# controller_ardu.net
KiCad netlist of a schematic drawn in EAGLE
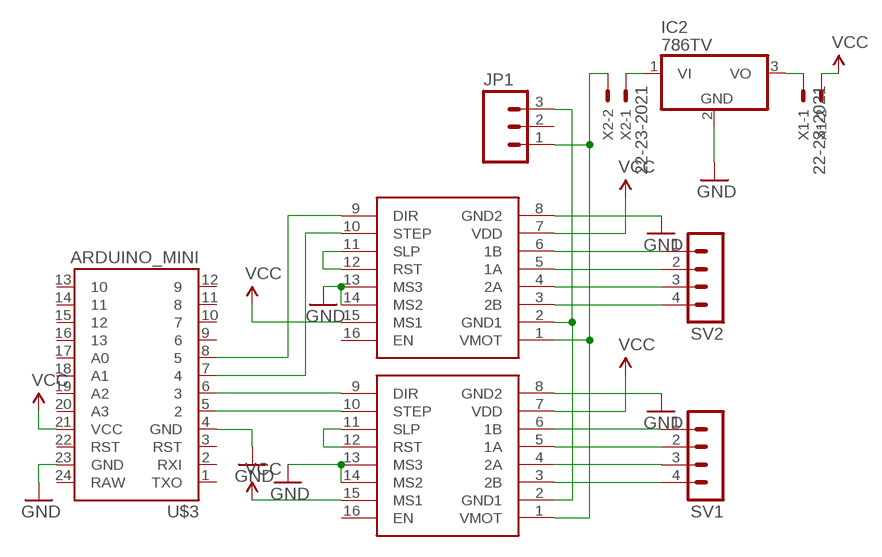
[diagram p0: schematic, sheet 1]

(export (version "E")
  (design (tool "Eeschema 10.0.6"))
  (components
    (comp (ref "IC2")
      (value "786TV")
      (footprint "eagle-import:TO220V")
      (libsource (lib "eagle-import") (part "78TV6"))
    )
    (comp (ref "JP1")
      (value "M03SCREW")
      (footprint "eagle-import:SCREWTERMINAL-3.5MM-3")
      (libsource (lib "eagle-import") (part "M03SCREW"))
    )
    (comp (ref "SV1")
      (value "MA04-1")
      (footprint "eagle-import:MA04-1")
      (libsource (lib "eagle-import") (part "MA04-1"))
    )
    (comp (ref "SV2")
      (value "MA04-1")
      (footprint "eagle-import:MA04-1")
      (libsource (lib "eagle-import") (part "MA04-1"))
    )
    (comp (ref "U$1")
      (value "POLOLUESTEPPERDRIVER")
      (footprint "eagle-import:DIL16")
      (libsource (lib "eagle-import") (part "POLOLUESTEPPERDRIVER"))
    )
    (comp (ref "U$2")
      (value "POLOLUESTEPPERDRIVER")
      (footprint "eagle-import:DIL16")
      (libsource (lib "eagle-import") (part "POLOLUESTEPPERDRIVER"))
    )
    (comp (ref "U$3")
      (value "ARDUINO_MINI")
      (footprint "eagle-import:ARDUINO_MINI")
      (libsource (lib "eagle-import") (part "ARDUINO_MINI"))
    )
    (comp (ref "X1")
      (value "22-23-2021")
      (footprint "eagle-import:22-23-2021")
      (fields (field (name "MF") "MOLEX"))
      (libsource (lib "eagle-import") (part "22-23-2021"))
    )
    (comp (ref "X2")
      (value "22-23-2021")
      (footprint "eagle-import:22-23-2021")
      (fields (field (name "MF") "MOLEX"))
      (libsource (lib "eagle-import") (part "22-23-2021"))
    )
  )
  (nets
    (net (code "1") (name "GND") (class "Default")
      (node (ref "IC2") (pin "2") (pinfunction "GND_2") (pintype "passive"))
      (node (ref "U$1") (pin "13") (pinfunction "MS3_13") (pintype "input"))
      (node (ref "U$1") (pin "14") (pinfunction "MS2_14") (pintype "input"))
      (node (ref "U$1") (pin "8") (pinfunction "GND2_8") (pintype "power_in"))
      (node (ref "U$2") (pin "13") (pinfunction "MS3_13") (pintype "input"))
      (node (ref "U$2") (pin "14") (pinfunction "MS2_14") (pintype "input"))
      (node (ref "U$2") (pin "8") (pinfunction "GND2_8") (pintype "power_in"))
      (node (ref "U$3") (pin "23") (pinfunction "GND_23") (pintype "bidirectional"))
      (node (ref "U$3") (pin "4") (pinfunction "GND_4") (pintype "bidirectional"))
    )
    (net (code "2") (name "Net-(IC2-VI)") (class "Default")
      (node (ref "IC2") (pin "1") (pinfunction "VI_1") (pintype "input"))
      (node (ref "X2") (pin "1") (pinfunction "S_1") (pintype "passive"))
    )
    (net (code "3") (name "Net-(IC2-VO)") (class "Default")
      (node (ref "IC2") (pin "3") (pinfunction "VO_3") (pintype "passive"))
      (node (ref "X1") (pin "1") (pinfunction "S_1") (pintype "passive"))
    )
    (net (code "4") (name "Net-(U$1-1A)") (class "Default")
      (node (ref "SV1") (pin "2") (pinfunction "2_2") (pintype "passive"))
      (node (ref "U$1") (pin "5") (pinfunction "1A_5") (pintype "output"))
    )
    (net (code "5") (name "Net-(U$1-1B)") (class "Default")
      (node (ref "SV1") (pin "1") (pinfunction "1_1") (pintype "passive"))
      (node (ref "U$1") (pin "6") (pinfunction "1B_6") (pintype "output"))
    )
    (net (code "6") (name "Net-(U$1-2A)") (class "Default")
      (node (ref "SV1") (pin "3") (pinfunction "3_3") (pintype "passive"))
      (node (ref "U$1") (pin "4") (pinfunction "2A_4") (pintype "output"))
    )
    (net (code "7") (name "Net-(U$1-2B)") (class "Default")
      (node (ref "SV1") (pin "4") (pinfunction "4_4") (pintype "passive"))
      (node (ref "U$1") (pin "3") (pinfunction "2B_3") (pintype "output"))
    )
    (net (code "8") (name "Net-(U$1-DIR)") (class "Default")
      (node (ref "U$1") (pin "9") (pinfunction "DIR_9") (pintype "input"))
      (node (ref "U$3") (pin "6") (pinfunction "3_6") (pintype "bidirectional"))
    )
    (net (code "9") (name "Net-(U$1-GND1)") (class "Default")
      (node (ref "JP1") (pin "3") (pinfunction "3_3") (pintype "passive"))
      (node (ref "U$1") (pin "2") (pinfunction "GND1_2") (pintype "power_in"))
      (node (ref "U$2") (pin "2") (pinfunction "GND1_2") (pintype "power_in"))
    )
    (net (code "10") (name "Net-(U$1-RST)") (class "Default")
      (node (ref "U$1") (pin "11") (pinfunction "SLP_11") (pintype "input"))
      (node (ref "U$1") (pin "12") (pinfunction "RST_12") (pintype "input"))
    )
    (net (code "11") (name "Net-(U$1-STEP)") (class "Default")
      (node (ref "U$1") (pin "10") (pinfunction "STEP_10") (pintype "input"))
      (node (ref "U$3") (pin "5") (pinfunction "2_5") (pintype "bidirectional"))
    )
    (net (code "12") (name "Net-(U$1-VMOT)") (class "Default")
      (node (ref "JP1") (pin "1") (pinfunction "1_1") (pintype "passive"))
      (node (ref "U$1") (pin "1") (pinfunction "VMOT_1") (pintype "power_in"))
      (node (ref "U$2") (pin "1") (pinfunction "VMOT_1") (pintype "power_in"))
      (node (ref "X2") (pin "2") (pinfunction "S_2") (pintype "passive"))
    )
    (net (code "13") (name "Net-(U$2-1A)") (class "Default")
      (node (ref "SV2") (pin "2") (pinfunction "2_2") (pintype "passive"))
      (node (ref "U$2") (pin "5") (pinfunction "1A_5") (pintype "output"))
    )
    (net (code "14") (name "Net-(U$2-1B)") (class "Default")
      (node (ref "SV2") (pin "1") (pinfunction "1_1") (pintype "passive"))
      (node (ref "U$2") (pin "6") (pinfunction "1B_6") (pintype "output"))
    )
    (net (code "15") (name "Net-(U$2-2A)") (class "Default")
      (node (ref "SV2") (pin "3") (pinfunction "3_3") (pintype "passive"))
      (node (ref "U$2") (pin "4") (pinfunction "2A_4") (pintype "output"))
    )
    (net (code "16") (name "Net-(U$2-2B)") (class "Default")
      (node (ref "SV2") (pin "4") (pinfunction "4_4") (pintype "passive"))
      (node (ref "U$2") (pin "3") (pinfunction "2B_3") (pintype "output"))
    )
    (net (code "17") (name "Net-(U$2-DIR)") (class "Default")
      (node (ref "U$2") (pin "9") (pinfunction "DIR_9") (pintype "input"))
      (node (ref "U$3") (pin "8") (pinfunction "5_8") (pintype "bidirectional"))
    )
    (net (code "18") (name "Net-(U$2-RST)") (class "Default")
      (node (ref "U$2") (pin "11") (pinfunction "SLP_11") (pintype "input"))
      (node (ref "U$2") (pin "12") (pinfunction "RST_12") (pintype "input"))
    )
    (net (code "19") (name "Net-(U$2-STEP)") (class "Default")
      (node (ref "U$2") (pin "10") (pinfunction "STEP_10") (pintype "input"))
      (node (ref "U$3") (pin "7") (pinfunction "4_7") (pintype "bidirectional"))
    )
    (net (code "20") (name "VCC") (class "Default")
      (node (ref "U$1") (pin "15") (pinfunction "MS1_15") (pintype "input"))
      (node (ref "U$1") (pin "7") (pinfunction "VDD_7") (pintype "power_in"))
      (node (ref "U$2") (pin "15") (pinfunction "MS1_15") (pintype "input"))
      (node (ref "U$2") (pin "7") (pinfunction "VDD_7") (pintype "power_in"))
      (node (ref "U$3") (pin "21") (pinfunction "VCC_21") (pintype "bidirectional"))
      (node (ref "X1") (pin "2") (pinfunction "S_2") (pintype "passive"))
    )
    (net (code "21") (name "unconnected-(JP1-Pad2)") (class "Default")
      (node (ref "JP1") (pin "2") (pinfunction "2_2") (pintype "passive"))
    )
    (net (code "22") (name "unconnected-(U$1-EN-Pad16)") (class "Default")
      (node (ref "U$1") (pin "16") (pinfunction "EN_16") (pintype "input"))
    )
    (net (code "23") (name "unconnected-(U$2-EN-Pad16)") (class "Default")
      (node (ref "U$2") (pin "16") (pinfunction "EN_16") (pintype "input"))
    )
    (net (code "24") (name "unconnected-(U$3-6-Pad9)") (class "Default")
      (node (ref "U$3") (pin "9") (pinfunction "6_9") (pintype "bidirectional"))
    )
    (net (code "25") (name "unconnected-(U$3-7-Pad10)") (class "Default")
      (node (ref "U$3") (pin "10") (pinfunction "7_10") (pintype "bidirectional"))
    )
    (net (code "26") (name "unconnected-(U$3-8-Pad11)") (class "Default")
      (node (ref "U$3") (pin "11") (pinfunction "8_11") (pintype "bidirectional"))
    )
    (net (code "27") (name "unconnected-(U$3-9-Pad12)") (class "Default")
      (node (ref "U$3") (pin "12") (pinfunction "9_12") (pintype "bidirectional"))
    )
    (net (code "28") (name "unconnected-(U$3-10-Pad13)") (class "Default")
      (node (ref "U$3") (pin "13") (pinfunction "10_13") (pintype "bidirectional"))
    )
    (net (code "29") (name "unconnected-(U$3-11-Pad14)") (class "Default")
      (node (ref "U$3") (pin "14") (pinfunction "11_14") (pintype "bidirectional"))
    )
    (net (code "30") (name "unconnected-(U$3-12-Pad15)") (class "Default")
      (node (ref "U$3") (pin "15") (pinfunction "12_15") (pintype "bidirectional"))
    )
    (net (code "31") (name "unconnected-(U$3-13-Pad16)") (class "Default")
      (node (ref "U$3") (pin "16") (pinfunction "13_16") (pintype "bidirectional"))
    )
    (net (code "32") (name "unconnected-(U$3-A0-Pad17)") (class "Default")
      (node (ref "U$3") (pin "17") (pinfunction "A0_17") (pintype "bidirectional"))
    )
    (net (code "33") (name "unconnected-(U$3-A1-Pad18)") (class "Default")
      (node (ref "U$3") (pin "18") (pinfunction "A1_18") (pintype "bidirectional"))
    )
    (net (code "34") (name "unconnected-(U$3-A2-Pad19)") (class "Default")
      (node (ref "U$3") (pin "19") (pinfunction "A2_19") (pintype "bidirectional"))
    )
    (net (code "35") (name "unconnected-(U$3-A3-Pad20)") (class "Default")
      (node (ref "U$3") (pin "20") (pinfunction "A3_20") (pintype "bidirectional"))
    )
    (net (code "36") (name "unconnected-(U$3-RAW-Pad24)") (class "Default")
      (node (ref "U$3") (pin "24") (pinfunction "RAW_24") (pintype "bidirectional"))
    )
    (net (code "37") (name "unconnected-(U$3-RST-Pad3)") (class "Default")
      (node (ref "U$3") (pin "3") (pinfunction "RST_3") (pintype "bidirectional"))
    )
    (net (code "38") (name "unconnected-(U$3-RST-Pad22)") (class "Default")
      (node (ref "U$3") (pin "22") (pinfunction "RST_22") (pintype "bidirectional"))
    )
    (net (code "39") (name "unconnected-(U$3-RXI-Pad2)") (class "Default")
      (node (ref "U$3") (pin "2") (pinfunction "RXI_2") (pintype "bidirectional"))
    )
    (net (code "40") (name "unconnected-(U$3-TXO-Pad1)") (class "Default")
      (node (ref "U$3") (pin "1") (pinfunction "TXO_1") (pintype "bidirectional"))
    )
  )
)
